# Altimeter.net
KiCad netlist of a schematic drawn in EAGLE
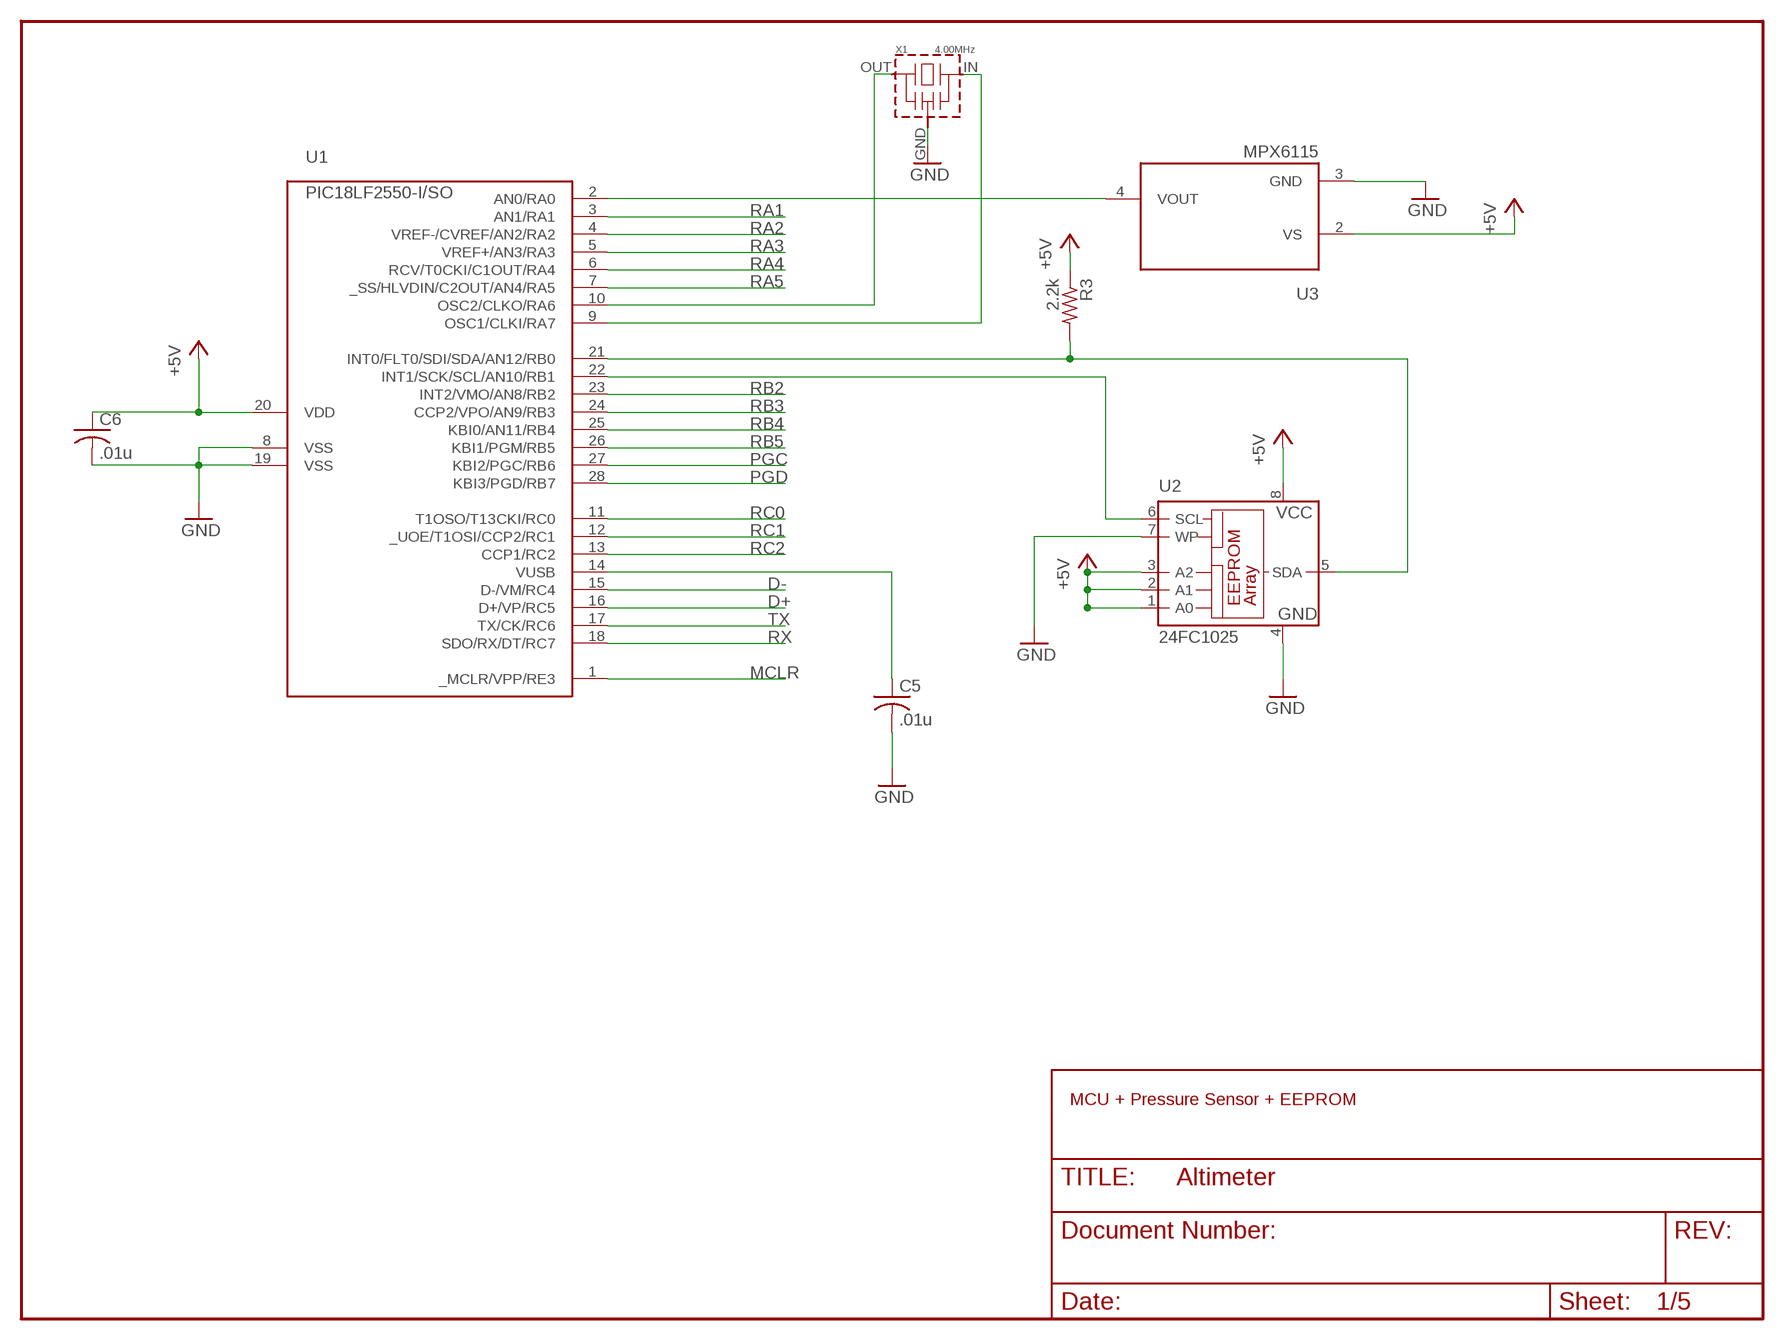
[diagram p0: schematic, sheet 1]
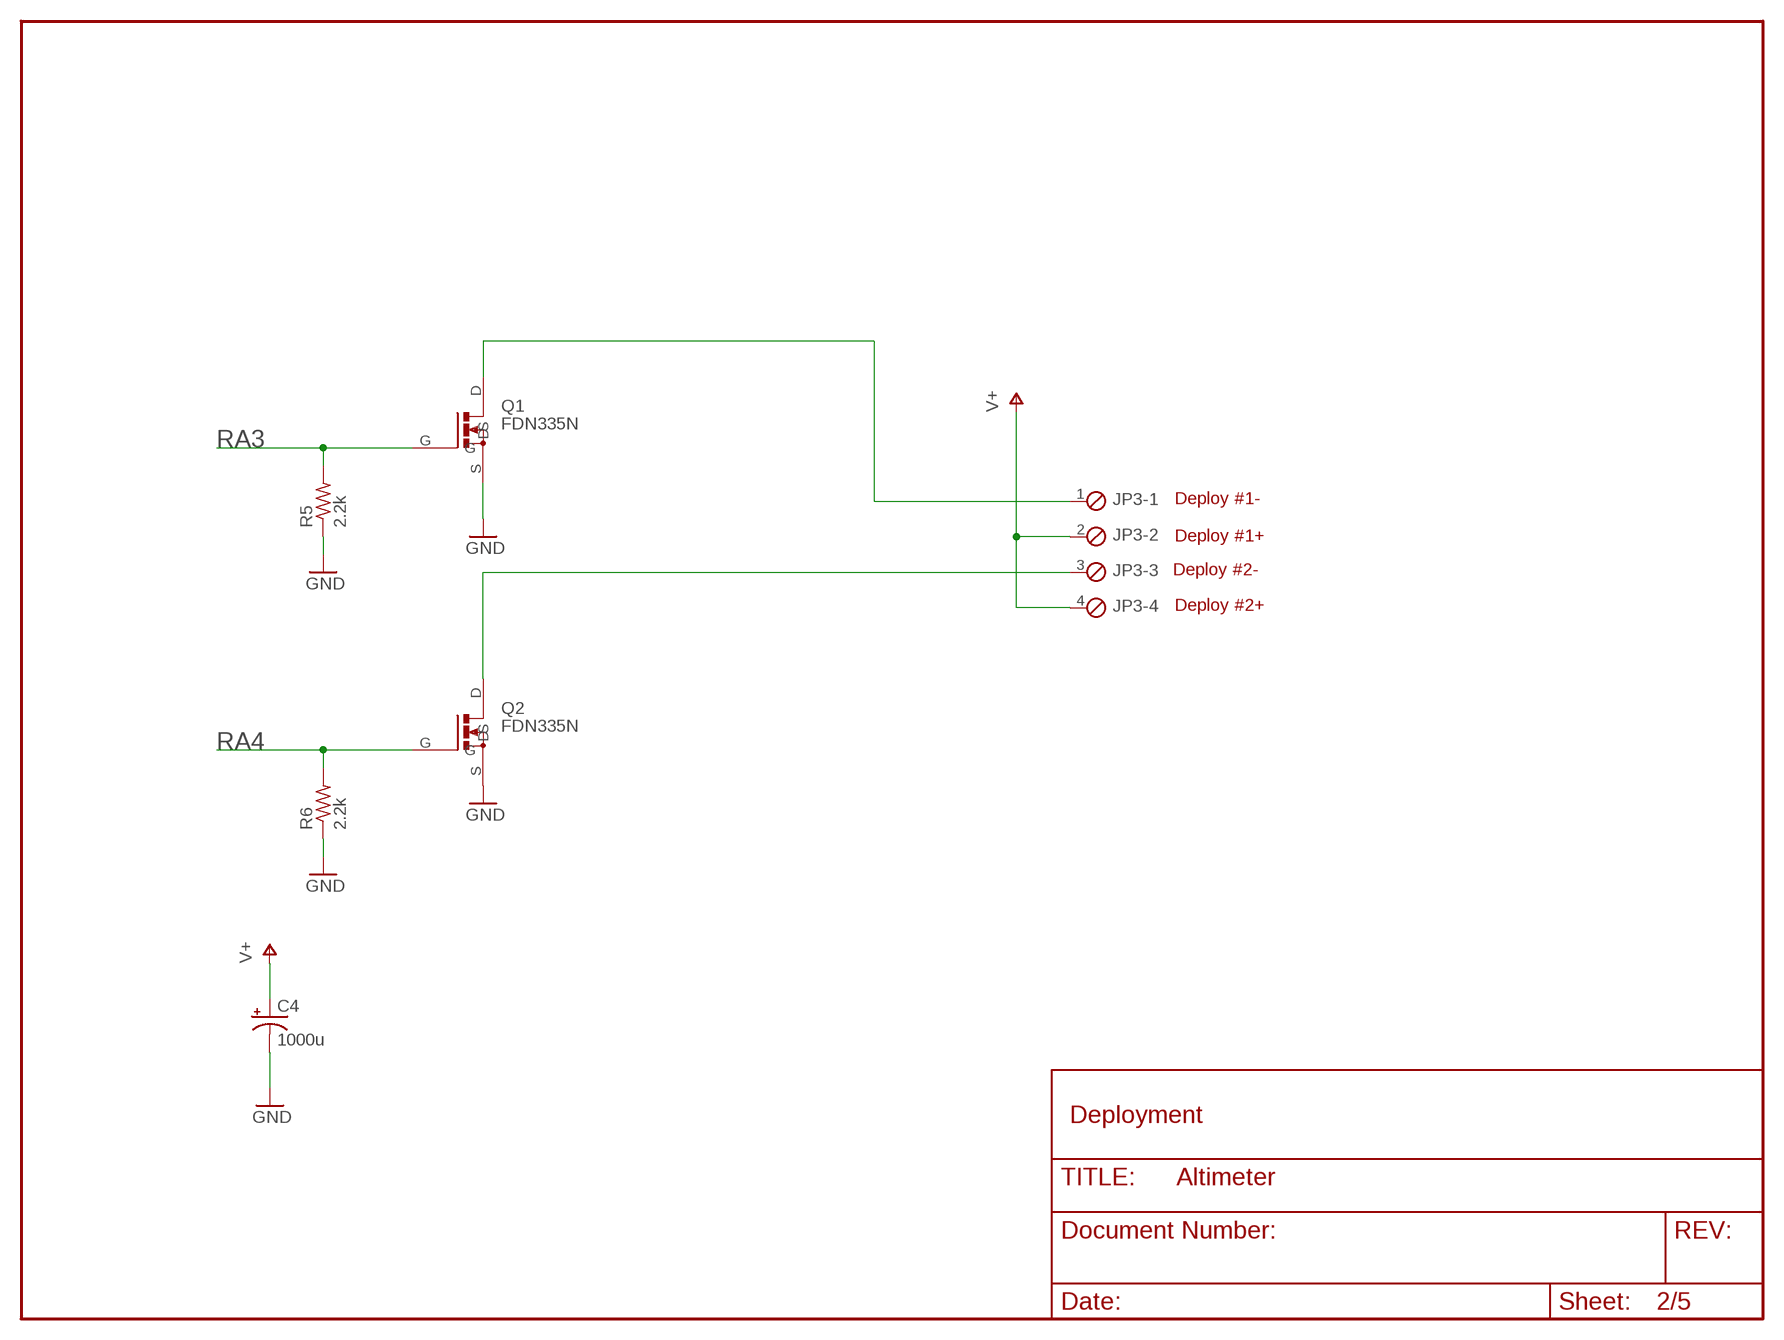
[diagram p1: schematic, sheet 2]
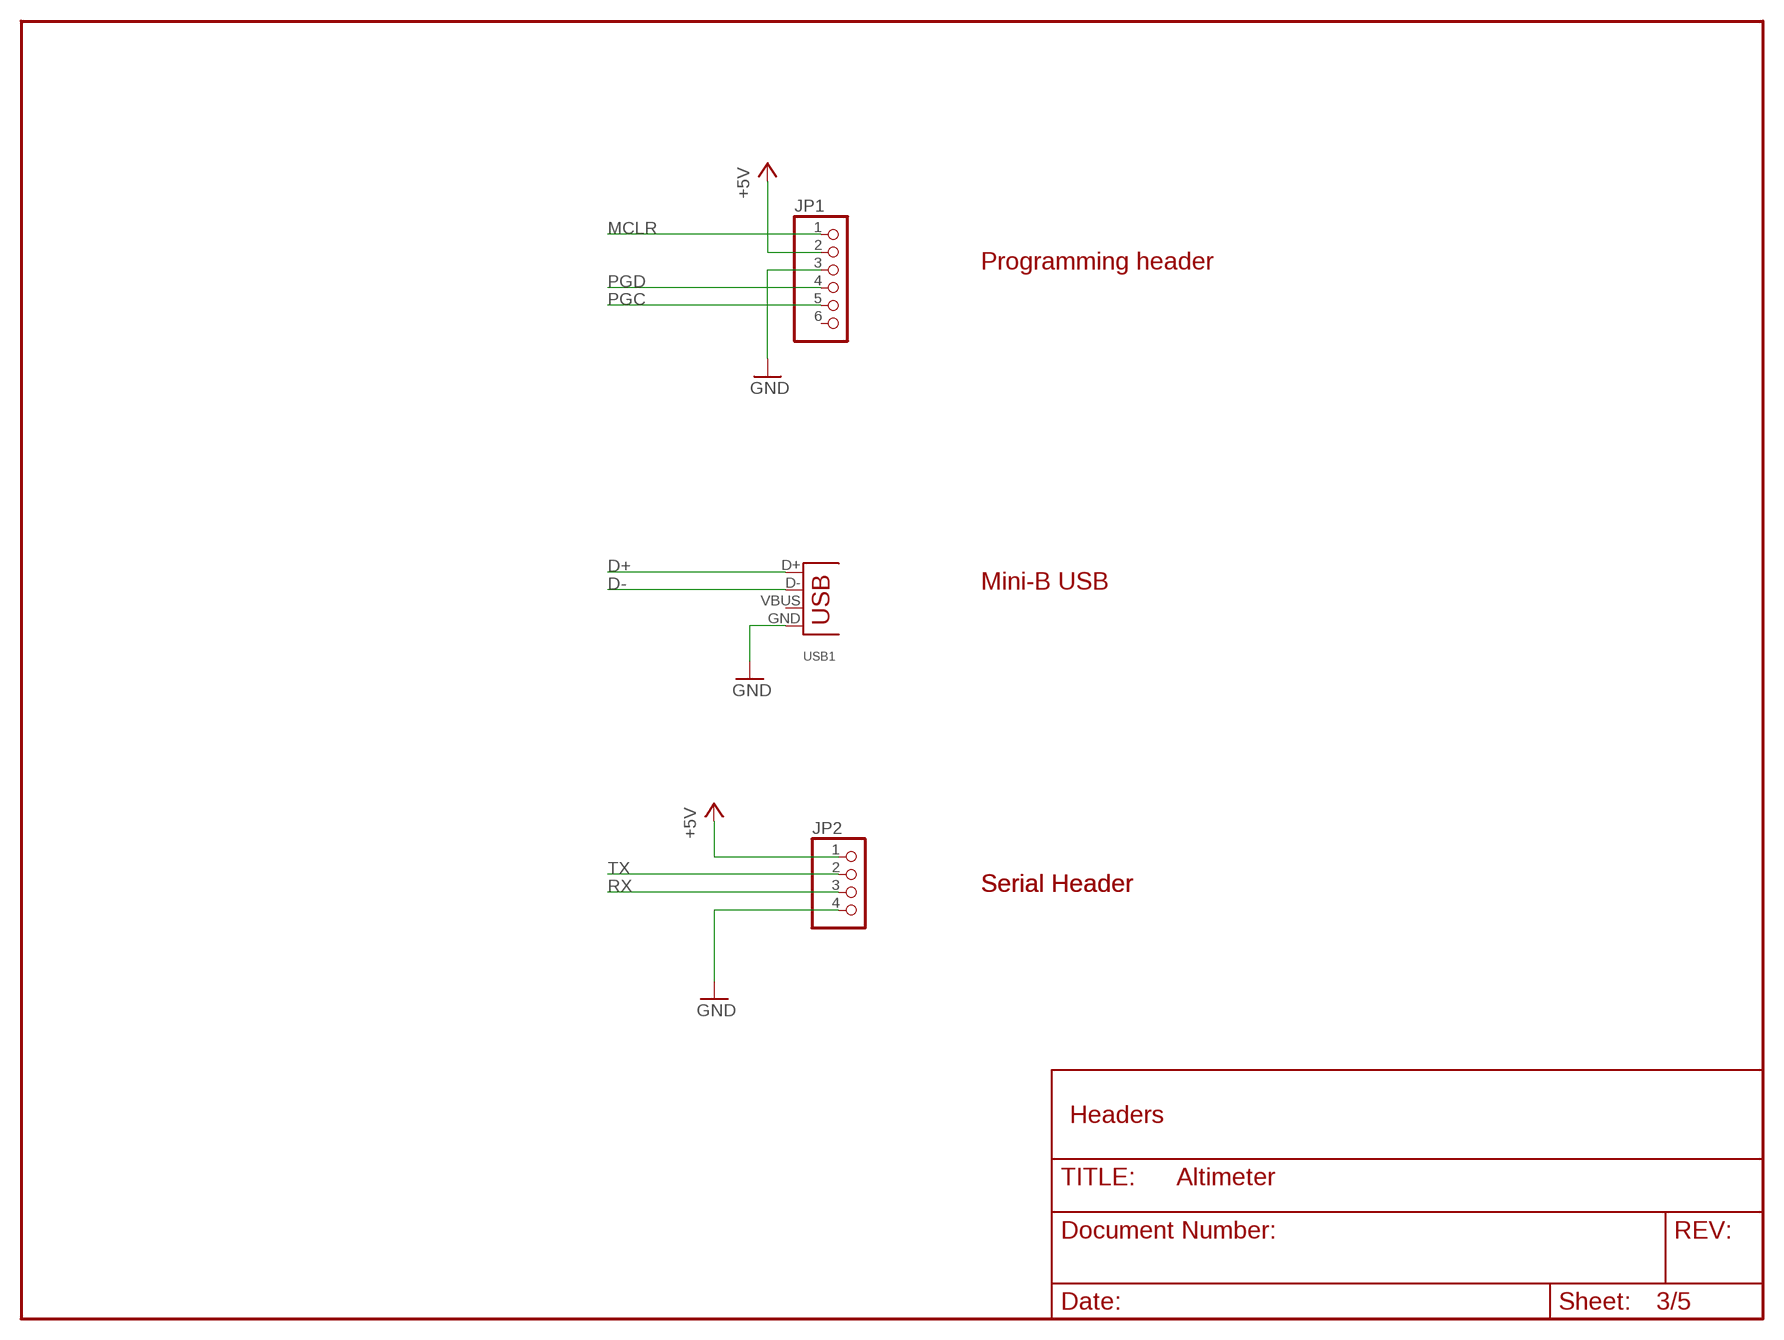
[diagram p2: schematic, sheet 3]
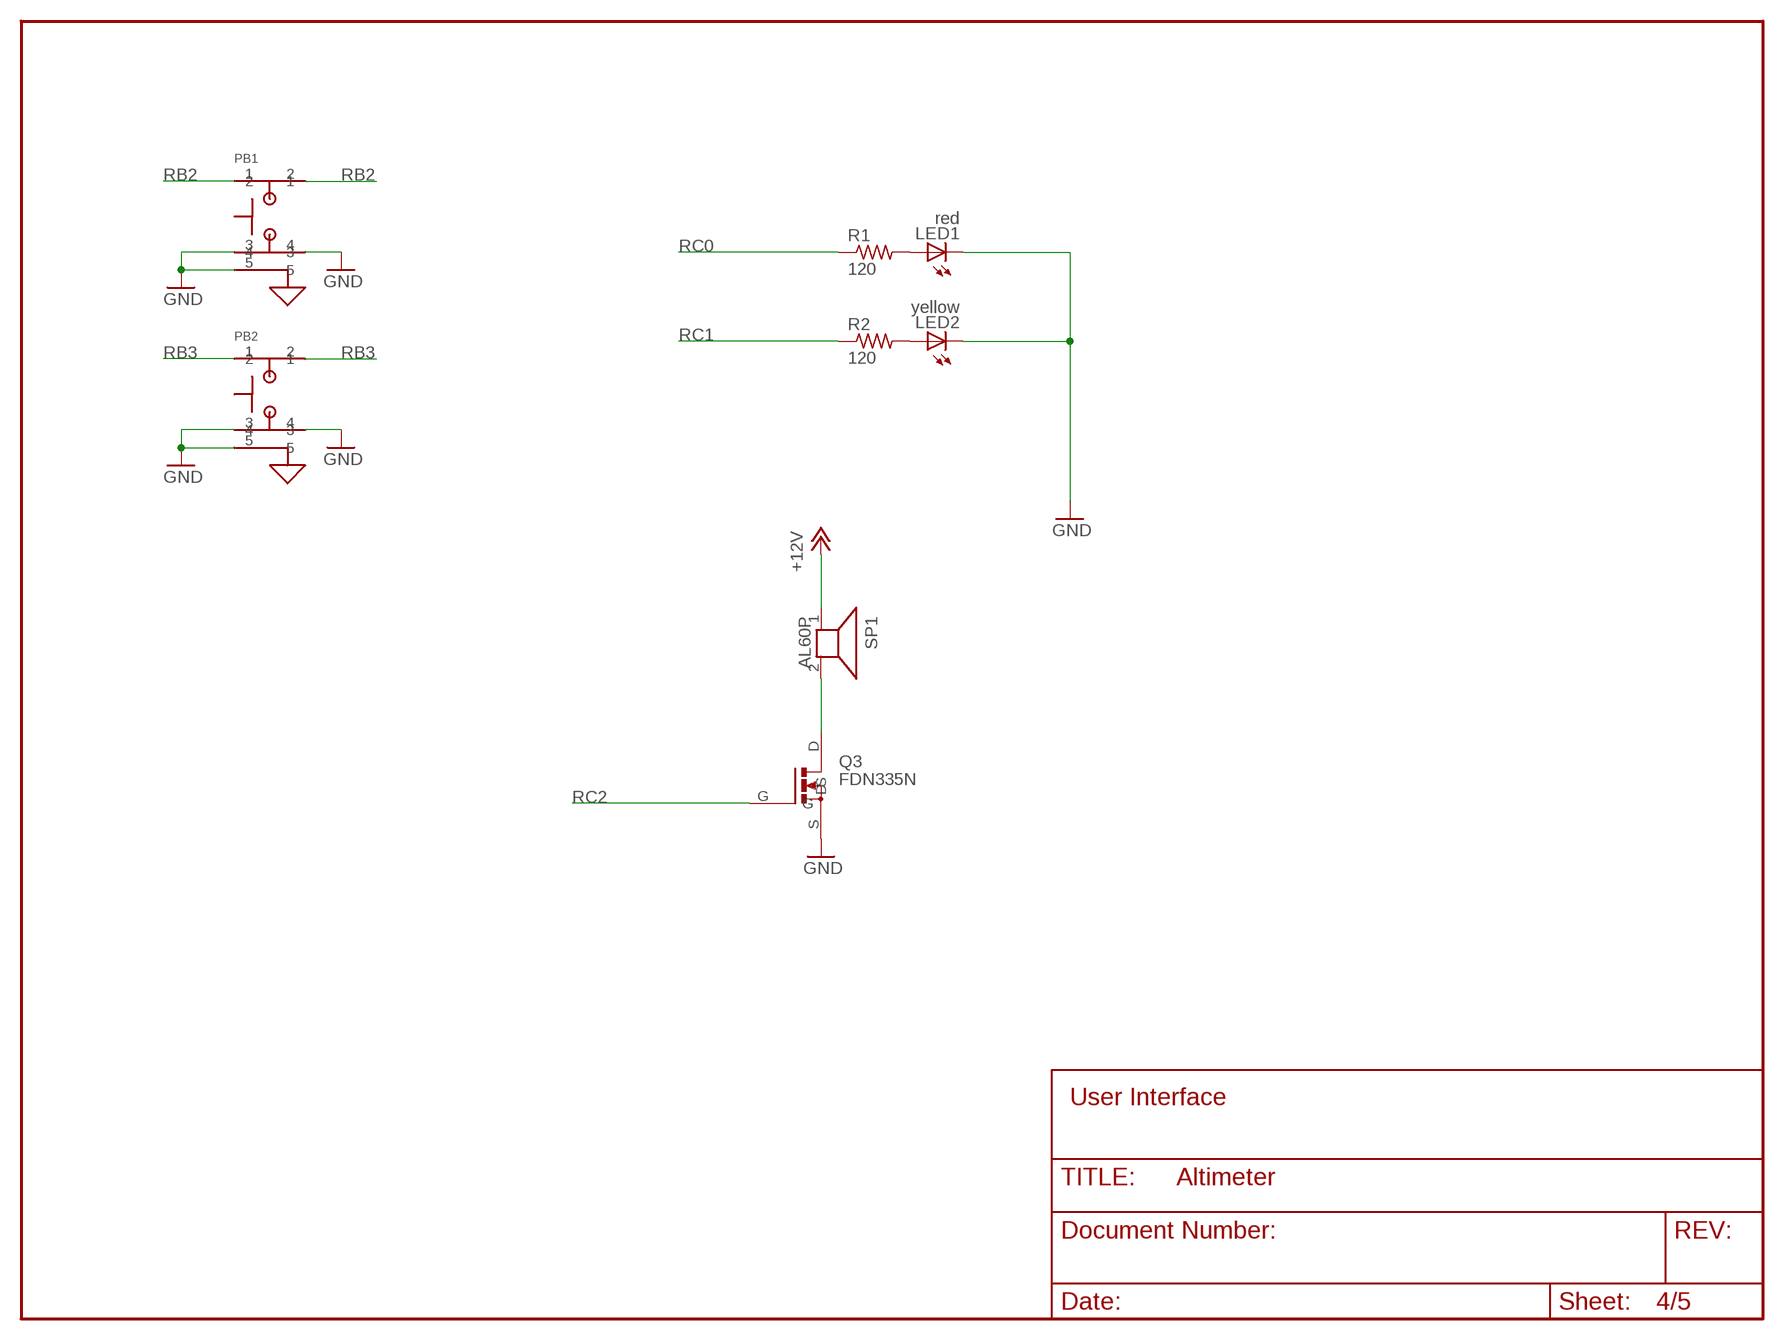
[diagram p3: schematic, sheet 4]
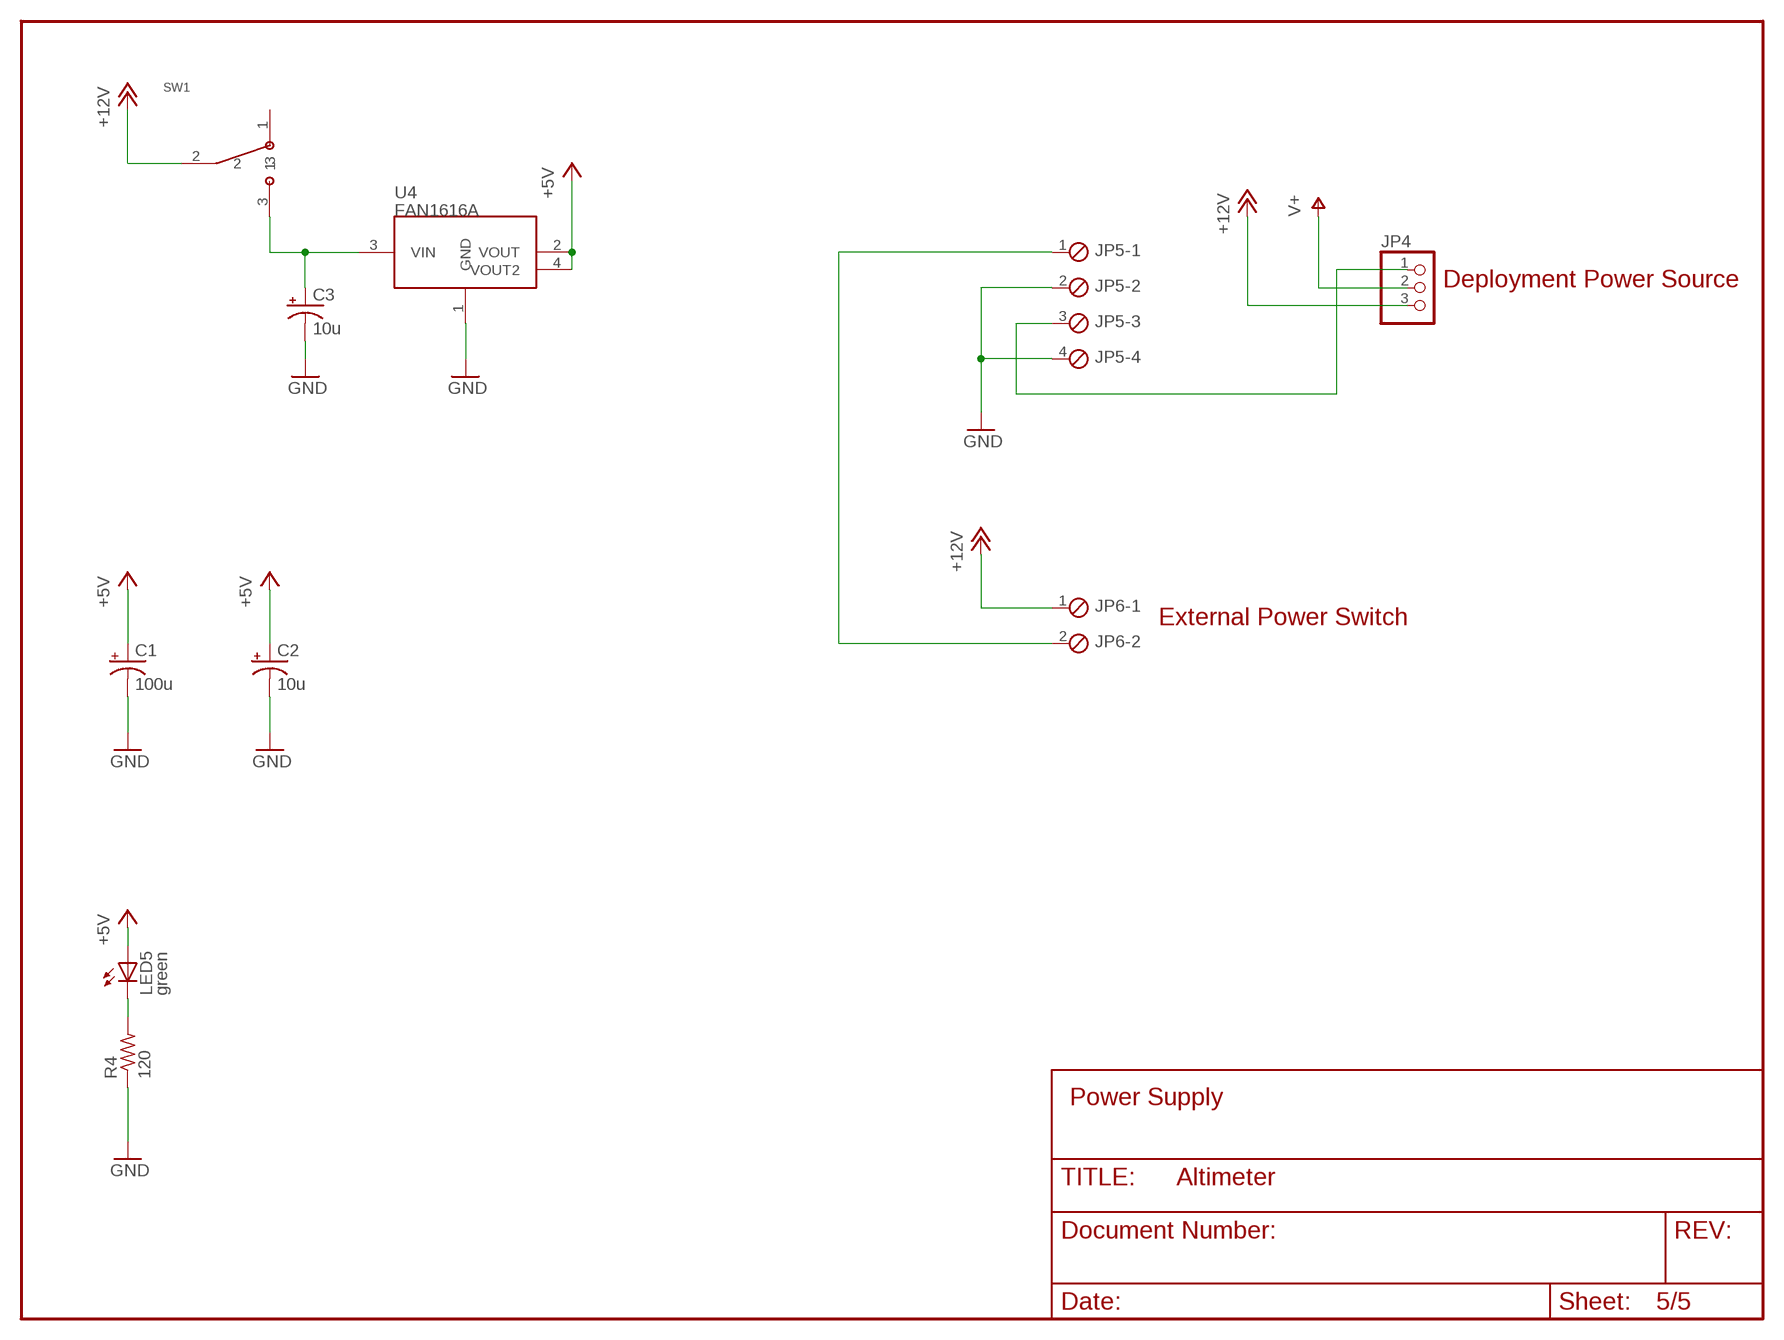
[diagram p4: schematic, sheet 5]

(export (version "E")
  (design (tool "Eeschema 10.0.6"))
  (components
    (comp (ref "C1")
      (value "100u")
      (footprint "eagle-import:PANASONIC_D")
      (libsource (lib "eagle-import") (part "CPOL-USD"))
    )
    (comp (ref "C2")
      (value "10u")
      (footprint "eagle-import:PANASONIC_C")
      (libsource (lib "eagle-import") (part "CPOL-USC"))
    )
    (comp (ref "C3")
      (value "10u")
      (footprint "eagle-import:PANASONIC_C")
      (libsource (lib "eagle-import") (part "CPOL-USC"))
    )
    (comp (ref "JP4")
      (value "PINHD-1X3")
      (footprint "eagle-import:1X03")
      (libsource (lib "eagle-import") (part "PINHD-1X3"))
    )
    (comp (ref "JP5")
      (value "MPT4")
      (footprint "eagle-import:4POL254")
      (libsource (lib "eagle-import") (part "MPT4"))
    )
    (comp (ref "JP6")
      (value "MPT2")
      (footprint "eagle-import:2POL254")
      (libsource (lib "eagle-import") (part "MPT2"))
    )
    (comp (ref "LED5")
      (value "green")
      (footprint "eagle-import:1206")
      (libsource (lib "eagle-import") (part "LEDSMT1206"))
    )
    (comp (ref "R4")
      (value "120")
      (footprint "eagle-import:R1206")
      (libsource (lib "eagle-import") (part "R-US_R1206"))
    )
    (comp (ref "SW1")
      (value "EG1218")
      (footprint "eagle-import:EG-SWITCH")
      (libsource (lib "eagle-import") (part "EG1218"))
    )
    (comp (ref "U4")
      (value "FAN1616A")
      (footprint "eagle-import:SOT223")
      (libsource (lib "eagle-import") (part "FAN1616A"))
    )
    (comp (ref "JP1")
      (value "PINHD-1X6")
      (footprint "eagle-import:1X06")
      (libsource (lib "eagle-import") (part "PINHD-1X6"))
    )
    (comp (ref "JP2")
      (value "PINHD-1X4")
      (footprint "eagle-import:1X04")
      (libsource (lib "eagle-import") (part "PINHD-1X4"))
    )
    (comp (ref "USB1")
      (value "USB-MB-S")
      (footprint "eagle-import:USB-MB-S")
      (libsource (lib "eagle-import") (part "USB-MB-S"))
    )
    (comp (ref "LED1")
      (value "red")
      (footprint "eagle-import:1206")
      (libsource (lib "eagle-import") (part "LEDSMT1206"))
    )
    (comp (ref "LED2")
      (value "yellow")
      (footprint "eagle-import:1206")
      (libsource (lib "eagle-import") (part "LEDSMT1206"))
    )
    (comp (ref "PB1")
      (value "ALPS_SWITCH_SMD")
      (footprint "eagle-import:ALPS-SMD-TACT")
      (libsource (lib "eagle-import") (part "ALPS_SWITCH_SMD"))
    )
    (comp (ref "PB2")
      (value "ALPS_SWITCH_SMD")
      (footprint "eagle-import:ALPS-SMD-TACT")
      (libsource (lib "eagle-import") (part "ALPS_SWITCH_SMD"))
    )
    (comp (ref "Q3")
      (value "FDN335N")
      (footprint "eagle-import:SSOT3")
      (libsource (lib "eagle-import") (part "FDN335N"))
    )
    (comp (ref "R1")
      (value "120")
      (footprint "eagle-import:R1206")
      (libsource (lib "eagle-import") (part "R-US_R1206"))
    )
    (comp (ref "R2")
      (value "120")
      (footprint "eagle-import:R1206")
      (libsource (lib "eagle-import") (part "R-US_R1206"))
    )
    (comp (ref "SP1")
      (value "AL60P")
      (footprint "eagle-import:KB-BUZZER")
      (libsource (lib "eagle-import") (part "AL60P"))
    )
    (comp (ref "C4")
      (value "1000u")
      (footprint "eagle-import:PANASONIC_G")
      (libsource (lib "eagle-import") (part "rcl-2_CPOL-USG"))
    )
    (comp (ref "JP3")
      (value "MPT4")
      (footprint "eagle-import:4POL254")
      (libsource (lib "eagle-import") (part "MPT4"))
    )
    (comp (ref "Q1")
      (value "FDN335N")
      (footprint "eagle-import:SSOT3")
      (libsource (lib "eagle-import") (part "FDN335N"))
    )
    (comp (ref "Q2")
      (value "FDN335N")
      (footprint "eagle-import:SSOT3")
      (libsource (lib "eagle-import") (part "FDN335N"))
    )
    (comp (ref "R5")
      (value "2.2k")
      (footprint "eagle-import:R1206")
      (libsource (lib "eagle-import") (part "R-US_R1206"))
    )
    (comp (ref "R6")
      (value "2.2k")
      (footprint "eagle-import:R1206")
      (libsource (lib "eagle-import") (part "R-US_R1206"))
    )
    (comp (ref "C5")
      (value ".01u")
      (footprint "eagle-import:C1206")
      (libsource (lib "eagle-import") (part "C-USC1206"))
    )
    (comp (ref "C6")
      (value ".01u")
      (footprint "eagle-import:C1206")
      (libsource (lib "eagle-import") (part "C-USC1206"))
    )
    (comp (ref "R3")
      (value "2.2k")
      (footprint "eagle-import:R1206")
      (libsource (lib "eagle-import") (part "R-US_R1206"))
    )
    (comp (ref "U1")
      (value "PIC18LF2550-I/SO")
      (footprint "eagle-import:SO-28W")
      (libsource (lib "eagle-import") (part "PIC182550-I/SOLF"))
    )
    (comp (ref "U2")
      (value "24FC1025")
      (footprint "eagle-import:SO-08M")
      (libsource (lib "eagle-import") (part "24SMLC128"))
    )
    (comp (ref "U3")
      (value "MPX6115")
      (footprint "eagle-import:SSOP8")
      (libsource (lib "eagle-import") (part "MPX6115"))
    )
    (comp (ref "X1")
      (value "4.00MHz")
      (footprint "eagle-import:7434")
      (libsource (lib "eagle-import") (part "CERAMIC_RES"))
    )
  )
  (nets
    (net (code "1") (name "+5V") (class "Default")
      (node (ref "C1") (pin "+") (pinfunction "+_+") (pintype "passive"))
      (node (ref "C2") (pin "+") (pinfunction "+_+") (pintype "passive"))
      (node (ref "C6") (pin "1") (pinfunction "1_1") (pintype "passive"))
      (node (ref "JP1") (pin "2") (pinfunction "2_2") (pintype "passive"))
      (node (ref "JP2") (pin "1") (pinfunction "1_1") (pintype "passive"))
      (node (ref "LED5") (pin "A") (pinfunction "A_A") (pintype "passive"))
      (node (ref "R3") (pin "1") (pinfunction "1_1") (pintype "passive"))
      (node (ref "U1") (pin "20") (pinfunction "VDD_20") (pintype "power_in"))
      (node (ref "U2") (pin "1") (pinfunction "A0_1") (pintype "input"))
      (node (ref "U2") (pin "2") (pinfunction "A1_2") (pintype "input"))
      (node (ref "U2") (pin "3") (pinfunction "A2_3") (pintype "input"))
      (node (ref "U2") (pin "8") (pinfunction "VCC_8") (pintype "power_in"))
      (node (ref "U3") (pin "2") (pinfunction "VS_2") (pintype "power_in"))
      (node (ref "U4") (pin "2") (pinfunction "VOUT_2") (pintype "bidirectional"))
      (node (ref "U4") (pin "4") (pinfunction "VOUT2_4") (pintype "bidirectional"))
    )
    (net (code "2") (name "+12V") (class "Default")
      (node (ref "JP4") (pin "3") (pinfunction "3_3") (pintype "passive"))
      (node (ref "JP6") (pin "1") (pinfunction "1_1") (pintype "passive"))
      (node (ref "SP1") (pin "1") (pinfunction "1_1") (pintype "passive"))
      (node (ref "SW1") (pin "2") (pinfunction "2_2") (pintype "bidirectional"))
    )
    (net (code "3") (name "D+") (class "Default")
      (node (ref "U1") (pin "16") (pinfunction "D+/VP/RC5_16") (pintype "bidirectional"))
      (node (ref "USB1") (pin "D+") (pinfunction "D+_D+") (pintype "bidirectional"))
    )
    (net (code "4") (name "D-") (class "Default")
      (node (ref "U1") (pin "15") (pinfunction "D-/VM/RC4_15") (pintype "bidirectional"))
      (node (ref "USB1") (pin "D-") (pinfunction "D-_D-") (pintype "bidirectional"))
    )
    (net (code "5") (name "GND") (class "Default")
      (node (ref "C1") (pin "-") (pinfunction "-_-") (pintype "passive"))
      (node (ref "C2") (pin "-") (pinfunction "-_-") (pintype "passive"))
      (node (ref "C3") (pin "-") (pinfunction "-_-") (pintype "passive"))
      (node (ref "C4") (pin "-") (pinfunction "-_-") (pintype "passive"))
      (node (ref "C5") (pin "2") (pinfunction "2_2") (pintype "passive"))
      (node (ref "C6") (pin "2") (pinfunction "2_2") (pintype "passive"))
      (node (ref "JP1") (pin "3") (pinfunction "3_3") (pintype "passive"))
      (node (ref "JP2") (pin "4") (pinfunction "4_4") (pintype "passive"))
      (node (ref "JP5") (pin "2") (pinfunction "1_2") (pintype "passive"))
      (node (ref "JP5") (pin "4") (pinfunction "1_4") (pintype "passive"))
      (node (ref "LED1") (pin "C") (pinfunction "C_C") (pintype "passive"))
      (node (ref "LED2") (pin "C") (pinfunction "C_C") (pintype "passive"))
      (node (ref "PB1") (pin "3") (pinfunction "3_3") (pintype "bidirectional"))
      (node (ref "PB1") (pin "4") (pinfunction "4_4") (pintype "bidirectional"))
      (node (ref "PB1") (pin "5") (pinfunction "5_5") (pintype "bidirectional"))
      (node (ref "PB2") (pin "3") (pinfunction "3_3") (pintype "bidirectional"))
      (node (ref "PB2") (pin "4") (pinfunction "4_4") (pintype "bidirectional"))
      (node (ref "PB2") (pin "5") (pinfunction "5_5") (pintype "bidirectional"))
      (node (ref "Q1") (pin "S") (pinfunction "S_S") (pintype "bidirectional"))
      (node (ref "Q2") (pin "S") (pinfunction "S_S") (pintype "bidirectional"))
      (node (ref "Q3") (pin "S") (pinfunction "S_S") (pintype "bidirectional"))
      (node (ref "R4") (pin "1") (pinfunction "1_1") (pintype "passive"))
      (node (ref "R5") (pin "1") (pinfunction "1_1") (pintype "passive"))
      (node (ref "R6") (pin "1") (pinfunction "1_1") (pintype "passive"))
      (node (ref "U1") (pin "19") (pinfunction "VSS_19") (pintype "power_in"))
      (node (ref "U1") (pin "8") (pinfunction "VSS_8") (pintype "power_in"))
      (node (ref "U2") (pin "4") (pinfunction "GND_4") (pintype "power_in"))
      (node (ref "U2") (pin "7") (pinfunction "WP_7") (pintype "input"))
      (node (ref "U3") (pin "3") (pinfunction "GND_3") (pintype "power_in"))
      (node (ref "U4") (pin "1") (pinfunction "GND_1") (pintype "bidirectional"))
      (node (ref "USB1") (pin "GND") (pinfunction "GND_GND") (pintype "bidirectional"))
      (node (ref "X1") (pin "GND") (pinfunction "VSS_GND") (pintype "power_in"))
    )
    (net (code "6") (name "MCLR") (class "Default")
      (node (ref "JP1") (pin "1") (pinfunction "1_1") (pintype "passive"))
      (node (ref "U1") (pin "1") (pinfunction "_MCLR/VPP/RE3_1") (pintype "input"))
    )
    (net (code "7") (name "Net-(JP3-Pad1)") (class "Default")
      (node (ref "JP3") (pin "1") (pinfunction "1_1") (pintype "passive"))
      (node (ref "Q1") (pin "D") (pinfunction "D_D") (pintype "bidirectional"))
    )
    (net (code "8") (name "Net-(JP3C-1)") (class "Default")
      (node (ref "JP3") (pin "3") (pinfunction "1_3") (pintype "passive"))
      (node (ref "Q2") (pin "D") (pinfunction "D_D") (pintype "bidirectional"))
    )
    (net (code "9") (name "Net-(JP5C-1)") (class "Default")
      (node (ref "JP4") (pin "1") (pinfunction "1_1") (pintype "passive"))
      (node (ref "JP5") (pin "3") (pinfunction "1_3") (pintype "passive"))
    )
    (net (code "10") (name "Net-(JP6B-1)") (class "Default")
      (node (ref "JP5") (pin "1") (pinfunction "1_1") (pintype "passive"))
      (node (ref "JP6") (pin "2") (pinfunction "1_2") (pintype "passive"))
    )
    (net (code "11") (name "Net-(LED1-PadA)") (class "Default")
      (node (ref "LED1") (pin "A") (pinfunction "A_A") (pintype "passive"))
      (node (ref "R1") (pin "2") (pinfunction "2_2") (pintype "passive"))
    )
    (net (code "12") (name "Net-(LED2-PadA)") (class "Default")
      (node (ref "LED2") (pin "A") (pinfunction "A_A") (pintype "passive"))
      (node (ref "R2") (pin "2") (pinfunction "2_2") (pintype "passive"))
    )
    (net (code "13") (name "Net-(LED5-PadC)") (class "Default")
      (node (ref "LED5") (pin "C") (pinfunction "C_C") (pintype "passive"))
      (node (ref "R4") (pin "2") (pinfunction "2_2") (pintype "passive"))
    )
    (net (code "14") (name "Net-(Q3-PadD)") (class "Default")
      (node (ref "Q3") (pin "D") (pinfunction "D_D") (pintype "bidirectional"))
      (node (ref "SP1") (pin "2") (pinfunction "2_2") (pintype "passive"))
    )
    (net (code "15") (name "Net-(U1-AN0{slash}RA0)") (class "Default")
      (node (ref "U1") (pin "2") (pinfunction "AN0/RA0_2") (pintype "bidirectional"))
      (node (ref "U3") (pin "4") (pinfunction "VOUT_4") (pintype "bidirectional"))
    )
    (net (code "16") (name "Net-(U1-INT0{slash}FLT0{slash}SDI{slash}SDA{slash}AN12{slash}RB0)") (class "Default")
      (node (ref "R3") (pin "2") (pinfunction "2_2") (pintype "passive"))
      (node (ref "U1") (pin "21") (pinfunction "INT0/FLT0/SDI/SDA/AN12/RB0_21") (pintype "bidirectional"))
      (node (ref "U2") (pin "5") (pinfunction "SDA_5") (pintype "bidirectional"))
    )
    (net (code "17") (name "Net-(U1-INT1{slash}SCK{slash}SCL{slash}AN10{slash}RB1)") (class "Default")
      (node (ref "U1") (pin "22") (pinfunction "INT1/SCK/SCL/AN10/RB1_22") (pintype "bidirectional"))
      (node (ref "U2") (pin "6") (pinfunction "SCL_6") (pintype "input"))
    )
    (net (code "18") (name "Net-(U1-OSC1{slash}CLKI{slash}RA7)") (class "Default")
      (node (ref "U1") (pin "9") (pinfunction "OSC1/CLKI/RA7_9") (pintype "bidirectional"))
      (node (ref "X1") (pin "IN") (pinfunction "3_IN") (pintype "input"))
    )
    (net (code "19") (name "Net-(U1-OSC2{slash}CLKO{slash}RA6)") (class "Default")
      (node (ref "U1") (pin "10") (pinfunction "OSC2/CLKO/RA6_10") (pintype "bidirectional"))
      (node (ref "X1") (pin "OUT") (pinfunction "1_OUT") (pintype "output"))
    )
    (net (code "20") (name "Net-(U1-VUSB)") (class "Default")
      (node (ref "C5") (pin "1") (pinfunction "1_1") (pintype "passive"))
      (node (ref "U1") (pin "14") (pinfunction "VUSB_14") (pintype "bidirectional"))
    )
    (net (code "21") (name "Net-(U4-VIN)") (class "Default")
      (node (ref "C3") (pin "+") (pinfunction "+_+") (pintype "passive"))
      (node (ref "SW1") (pin "3") (pinfunction "3_3") (pintype "bidirectional"))
      (node (ref "U4") (pin "3") (pinfunction "VIN_3") (pintype "bidirectional"))
    )
    (net (code "22") (name "PGC") (class "Default")
      (node (ref "JP1") (pin "5") (pinfunction "5_5") (pintype "passive"))
      (node (ref "U1") (pin "27") (pinfunction "KBI2/PGC/RB6_27") (pintype "bidirectional"))
    )
    (net (code "23") (name "PGD") (class "Default")
      (node (ref "JP1") (pin "4") (pinfunction "4_4") (pintype "passive"))
      (node (ref "U1") (pin "28") (pinfunction "KBI3/PGD/RB7_28") (pintype "bidirectional"))
    )
    (net (code "24") (name "RA1") (class "Default")
      (node (ref "U1") (pin "3") (pinfunction "AN1/RA1_3") (pintype "bidirectional"))
    )
    (net (code "25") (name "RA2") (class "Default")
      (node (ref "U1") (pin "4") (pinfunction "VREF-/CVREF/AN2/RA2_4") (pintype "bidirectional"))
    )
    (net (code "26") (name "RA3") (class "Default")
      (node (ref "Q1") (pin "G") (pinfunction "G_G") (pintype "bidirectional"))
      (node (ref "R5") (pin "2") (pinfunction "2_2") (pintype "passive"))
      (node (ref "U1") (pin "5") (pinfunction "VREF+/AN3/RA3_5") (pintype "bidirectional"))
    )
    (net (code "27") (name "RA4") (class "Default")
      (node (ref "Q2") (pin "G") (pinfunction "G_G") (pintype "bidirectional"))
      (node (ref "R6") (pin "2") (pinfunction "2_2") (pintype "passive"))
      (node (ref "U1") (pin "6") (pinfunction "RCV/T0CKI/C1OUT/RA4_6") (pintype "bidirectional"))
    )
    (net (code "28") (name "RA5") (class "Default")
      (node (ref "U1") (pin "7") (pinfunction "_SS/HLVDIN/C2OUT/AN4/RA5_7") (pintype "bidirectional"))
    )
    (net (code "29") (name "RB2") (class "Default")
      (node (ref "PB1") (pin "1") (pinfunction "1_1") (pintype "bidirectional"))
      (node (ref "PB1") (pin "2") (pinfunction "2_2") (pintype "bidirectional"))
      (node (ref "U1") (pin "23") (pinfunction "INT2/VMO/AN8/RB2_23") (pintype "bidirectional"))
    )
    (net (code "30") (name "RB3") (class "Default")
      (node (ref "PB2") (pin "1") (pinfunction "1_1") (pintype "bidirectional"))
      (node (ref "PB2") (pin "2") (pinfunction "2_2") (pintype "bidirectional"))
      (node (ref "U1") (pin "24") (pinfunction "CCP2/VPO/AN9/RB3_24") (pintype "bidirectional"))
    )
    (net (code "31") (name "RB4") (class "Default")
      (node (ref "U1") (pin "25") (pinfunction "KBI0/AN11/RB4_25") (pintype "bidirectional"))
    )
    (net (code "32") (name "RB5") (class "Default")
      (node (ref "U1") (pin "26") (pinfunction "KBI1/PGM/RB5_26") (pintype "bidirectional"))
    )
    (net (code "33") (name "RC0") (class "Default")
      (node (ref "R1") (pin "1") (pinfunction "1_1") (pintype "passive"))
      (node (ref "U1") (pin "11") (pinfunction "T1OSO/T13CKI/RC0_11") (pintype "bidirectional"))
    )
    (net (code "34") (name "RC1") (class "Default")
      (node (ref "R2") (pin "1") (pinfunction "1_1") (pintype "passive"))
      (node (ref "U1") (pin "12") (pinfunction "_UOE/T1OSI/CCP2/RC1_12") (pintype "bidirectional"))
    )
    (net (code "35") (name "RC2") (class "Default")
      (node (ref "Q3") (pin "G") (pinfunction "G_G") (pintype "bidirectional"))
      (node (ref "U1") (pin "13") (pinfunction "CCP1/RC2_13") (pintype "bidirectional"))
    )
    (net (code "36") (name "RX") (class "Default")
      (node (ref "JP2") (pin "3") (pinfunction "3_3") (pintype "passive"))
      (node (ref "U1") (pin "18") (pinfunction "SDO/RX/DT/RC7_18") (pintype "bidirectional"))
    )
    (net (code "37") (name "TX") (class "Default")
      (node (ref "JP2") (pin "2") (pinfunction "2_2") (pintype "passive"))
      (node (ref "U1") (pin "17") (pinfunction "TX/CK/RC6_17") (pintype "bidirectional"))
    )
    (net (code "38") (name "V+") (class "Default")
      (node (ref "C4") (pin "+") (pinfunction "+_+") (pintype "passive"))
      (node (ref "JP3") (pin "2") (pinfunction "1_2") (pintype "passive"))
      (node (ref "JP3") (pin "4") (pinfunction "1_4") (pintype "passive"))
      (node (ref "JP4") (pin "2") (pinfunction "2_2") (pintype "passive"))
    )
    (net (code "39") (name "unconnected-(JP1-Pad6)") (class "Default")
      (node (ref "JP1") (pin "6") (pinfunction "6_6") (pintype "passive"))
    )
    (net (code "40") (name "unconnected-(SW1-Pad1)") (class "Default")
      (node (ref "SW1") (pin "1") (pinfunction "1_1") (pintype "bidirectional"))
    )
    (net (code "41") (name "unconnected-(USB1-PadVBUS)") (class "Default")
      (node (ref "USB1") (pin "VBUS") (pinfunction "VBUS_VBUS") (pintype "bidirectional"))
    )
  )
)
